# dummy.net
KiCad netlist of a schematic drawn in EAGLE
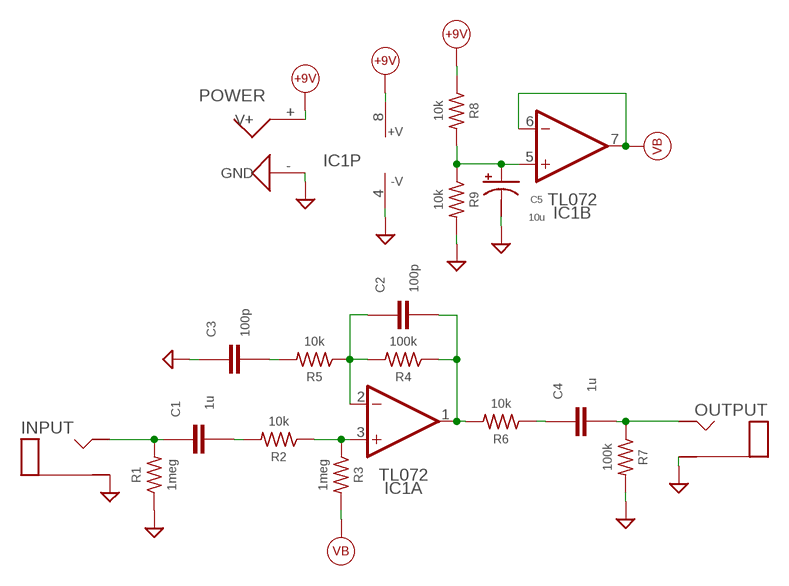
[diagram p0: schematic, sheet 1]

(export (version "E")
  (design (tool "Eeschema 10.0.6"))
  (components
    (comp (ref "C1")
      (value "1u")
      (footprint "eagle-import:0805")
      (libsource (lib "eagle-import") (part "CAPSMD"))
    )
    (comp (ref "C2")
      (value "100p")
      (footprint "eagle-import:0805")
      (libsource (lib "eagle-import") (part "CAPSMD"))
    )
    (comp (ref "C3")
      (value "100p")
      (footprint "eagle-import:0805")
      (libsource (lib "eagle-import") (part "CAPSMD"))
    )
    (comp (ref "C4")
      (value "1u")
      (footprint "eagle-import:0805")
      (libsource (lib "eagle-import") (part "CAPSMD"))
    )
    (comp (ref "C5")
      (value "10u")
      (footprint "eagle-import:4X4.5SMD")
      (libsource (lib "eagle-import") (part "ELECTROLYTIC"))
    )
    (comp (ref "IC1")
      (value "TL072")
      (footprint "eagle-import:SO08")
      (libsource (lib "eagle-import") (part "DUAL_OPAMPSMD"))
    )
    (comp (ref "INPUT")
      (value "generic")
      (footprint "eagle-import:TWO_PADS")
      (libsource (lib "eagle-import") (part "MONO"))
    )
    (comp (ref "OUTPUT")
      (value "generic")
      (footprint "eagle-import:TWO_PADS")
      (libsource (lib "eagle-import") (part "MONO"))
    )
    (comp (ref "POWER")
      (value "POWERJACK_PADS")
      (footprint "eagle-import:AB9V")
      (libsource (lib "eagle-import") (part "POWERJACK_PADS"))
    )
    (comp (ref "R1")
      (value "1meg")
      (footprint "eagle-import:0805")
      (libsource (lib "eagle-import") (part "RESISTOR0805"))
    )
    (comp (ref "R2")
      (value "10k")
      (footprint "eagle-import:0805")
      (libsource (lib "eagle-import") (part "RESISTOR0805"))
    )
    (comp (ref "R3")
      (value "1meg")
      (footprint "eagle-import:0805")
      (libsource (lib "eagle-import") (part "RESISTOR0805"))
    )
    (comp (ref "R4")
      (value "100k")
      (footprint "eagle-import:0805")
      (libsource (lib "eagle-import") (part "RESISTOR0805"))
    )
    (comp (ref "R5")
      (value "10k")
      (footprint "eagle-import:0805")
      (libsource (lib "eagle-import") (part "RESISTOR0805"))
    )
    (comp (ref "R6")
      (value "10k")
      (footprint "eagle-import:0805")
      (libsource (lib "eagle-import") (part "RESISTOR0805"))
    )
    (comp (ref "R7")
      (value "100k")
      (footprint "eagle-import:0805")
      (libsource (lib "eagle-import") (part "RESISTOR0805"))
    )
    (comp (ref "R8")
      (value "10k")
      (footprint "eagle-import:0805")
      (libsource (lib "eagle-import") (part "RESISTOR0805"))
    )
    (comp (ref "R9")
      (value "10k")
      (footprint "eagle-import:0805")
      (libsource (lib "eagle-import") (part "RESISTOR0805"))
    )
  )
  (nets
    (net (code "1") (name "+9V") (class "Default")
      (node (ref "IC1") (pin "8") (pinfunction "VDD_8") (pintype "power_in"))
      (node (ref "POWER") (pin "+") (pinfunction "V+_+") (pintype "bidirectional"))
      (node (ref "R8") (pin "1") (pinfunction "1_1") (pintype "passive"))
    )
    (net (code "2") (name "+VB") (class "Default")
      (node (ref "IC1") (pin "6") (pinfunction "-IN_6") (pintype "input"))
      (node (ref "IC1") (pin "7") (pinfunction "OUT_7") (pintype "output"))
      (node (ref "R3") (pin "2") (pinfunction "2_2") (pintype "passive"))
    )
    (net (code "3") (name "GND") (class "Default")
      (node (ref "C3") (pin "1") (pinfunction "1_1") (pintype "passive"))
      (node (ref "C5") (pin "P$2") (pinfunction "-_P$2") (pintype "passive"))
      (node (ref "IC1") (pin "4") (pinfunction "VSS_4") (pintype "power_in"))
      (node (ref "INPUT") (pin "S") (pinfunction "SLEEVE_S") (pintype "passive"))
      (node (ref "OUTPUT") (pin "S") (pinfunction "SLEEVE_S") (pintype "passive"))
      (node (ref "POWER") (pin "-") (pinfunction "GND_-") (pintype "bidirectional"))
      (node (ref "R1") (pin "1") (pinfunction "1_1") (pintype "passive"))
      (node (ref "R7") (pin "2") (pinfunction "2_2") (pintype "passive"))
      (node (ref "R9") (pin "2") (pinfunction "2_2") (pintype "passive"))
    )
    (net (code "4") (name "Net-(C1-Pad2)") (class "Default")
      (node (ref "C1") (pin "2") (pinfunction "2_2") (pintype "passive"))
      (node (ref "R2") (pin "2") (pinfunction "2_2") (pintype "passive"))
    )
    (net (code "5") (name "Net-(C3-Pad2)") (class "Default")
      (node (ref "C3") (pin "2") (pinfunction "2_2") (pintype "passive"))
      (node (ref "R5") (pin "2") (pinfunction "2_2") (pintype "passive"))
    )
    (net (code "6") (name "Net-(C4-Pad1)") (class "Default")
      (node (ref "C4") (pin "1") (pinfunction "1_1") (pintype "passive"))
      (node (ref "R6") (pin "1") (pinfunction "1_1") (pintype "passive"))
    )
    (net (code "7") (name "Net-(C5-+)") (class "Default")
      (node (ref "C5") (pin "P$1") (pinfunction "+_P$1") (pintype "passive"))
      (node (ref "IC1") (pin "5") (pinfunction "+IN_5") (pintype "input"))
      (node (ref "R8") (pin "2") (pinfunction "2_2") (pintype "passive"))
      (node (ref "R9") (pin "1") (pinfunction "1_1") (pintype "passive"))
    )
    (net (code "8") (name "Net-(IC1A-+IN)") (class "Default")
      (node (ref "IC1") (pin "3") (pinfunction "+IN_3") (pintype "input"))
      (node (ref "R2") (pin "1") (pinfunction "1_1") (pintype "passive"))
      (node (ref "R3") (pin "1") (pinfunction "1_1") (pintype "passive"))
    )
    (net (code "9") (name "Net-(IC1A--IN)") (class "Default")
      (node (ref "C2") (pin "1") (pinfunction "1_1") (pintype "passive"))
      (node (ref "IC1") (pin "2") (pinfunction "-IN_2") (pintype "input"))
      (node (ref "R4") (pin "2") (pinfunction "2_2") (pintype "passive"))
      (node (ref "R5") (pin "1") (pinfunction "1_1") (pintype "passive"))
    )
    (net (code "10") (name "Net-(IC1A-OUT)") (class "Default")
      (node (ref "C2") (pin "2") (pinfunction "2_2") (pintype "passive"))
      (node (ref "IC1") (pin "1") (pinfunction "OUT_1") (pintype "output"))
      (node (ref "R4") (pin "1") (pinfunction "1_1") (pintype "passive"))
      (node (ref "R6") (pin "2") (pinfunction "2_2") (pintype "passive"))
    )
    (net (code "11") (name "Net-(INPUT-TIP)") (class "Default")
      (node (ref "C1") (pin "1") (pinfunction "1_1") (pintype "passive"))
      (node (ref "INPUT") (pin "T") (pinfunction "TIP_T") (pintype "passive"))
      (node (ref "R1") (pin "2") (pinfunction "2_2") (pintype "passive"))
    )
    (net (code "12") (name "Net-(OUTPUT-TIP)") (class "Default")
      (node (ref "C4") (pin "2") (pinfunction "2_2") (pintype "passive"))
      (node (ref "OUTPUT") (pin "T") (pinfunction "TIP_T") (pintype "passive"))
      (node (ref "R7") (pin "1") (pinfunction "1_1") (pintype "passive"))
    )
  )
)
